# SimuRain_v1_0_UNO.net
KiCad netlist of a schematic drawn in EAGLE
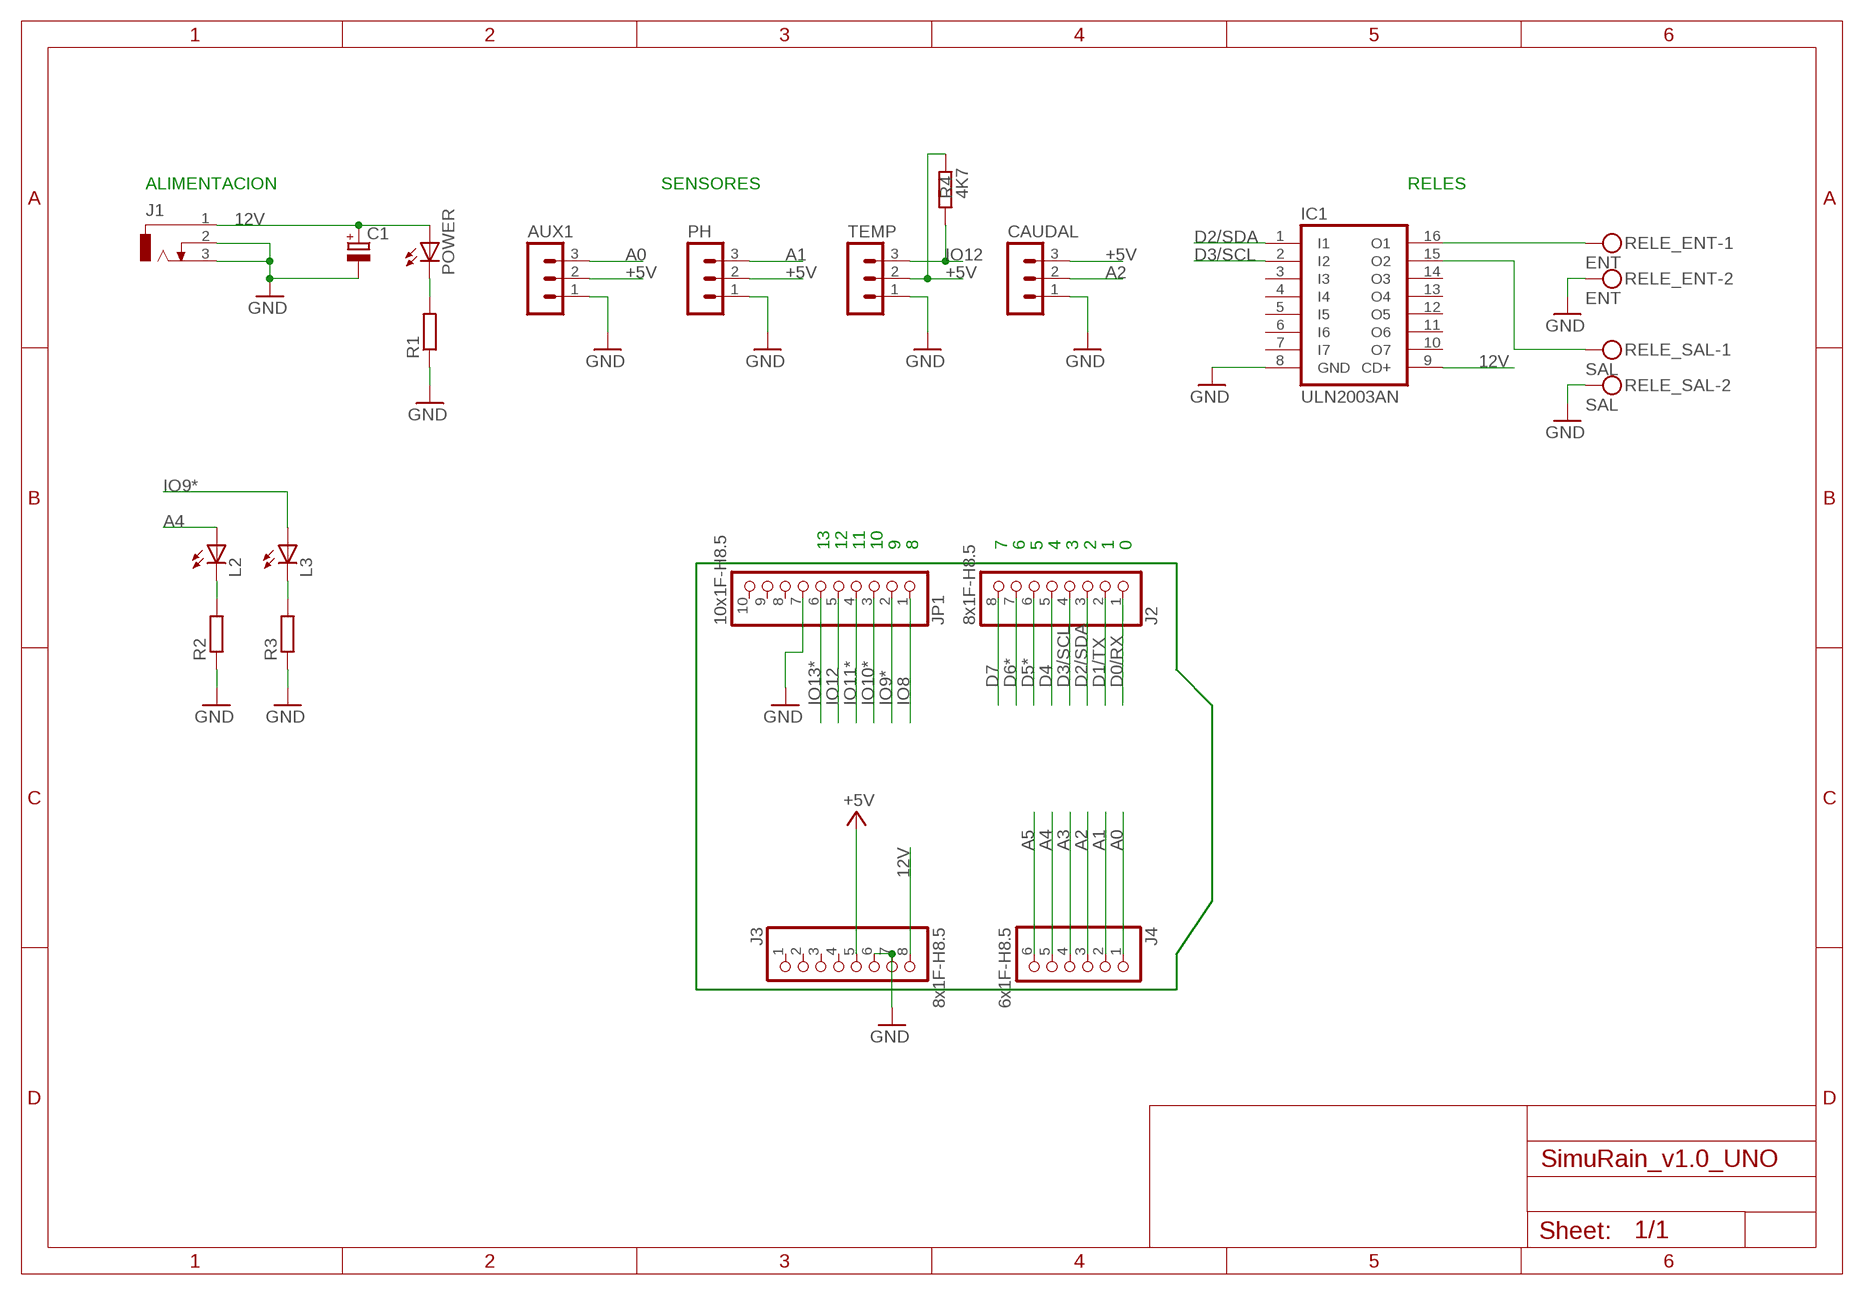
[diagram p0: schematic, sheet 1]

(export (version "E")
  (design (tool "Eeschema 10.0.6"))
  (components
    (comp (ref "AUX1")
      (value "MA03-1")
      (footprint "eagle-import:MA03-1")
      (libsource (lib "eagle-import") (part "MA03-1"))
    )
    (comp (ref "C1")
      (value "CPOL-EUE5-6")
      (footprint "eagle-import:E5-6")
      (libsource (lib "eagle-import") (part "CPOL-EUE5-6"))
    )
    (comp (ref "CAUDAL")
      (value "MA03-1")
      (footprint "eagle-import:MA03-1")
      (libsource (lib "eagle-import") (part "MA03-1"))
    )
    (comp (ref "IC1")
      (value "ULN2003AN")
      (footprint "eagle-import:DIL16")
      (libsource (lib "eagle-import") (part "ULN2003AN"))
    )
    (comp (ref "J1")
      (value "DCJ0303")
      (footprint "eagle-import:DCJ0303")
      (libsource (lib "eagle-import") (part "DCJ0303"))
    )
    (comp (ref "J2")
      (value "8x1F-H8.5")
      (footprint "eagle-import:1X08")
      (libsource (lib "eagle-import") (part "PINHD-1X8"))
    )
    (comp (ref "J3")
      (value "8x1F-H8.5")
      (footprint "eagle-import:1X08")
      (libsource (lib "eagle-import") (part "PINHD-1X8"))
    )
    (comp (ref "J4")
      (value "6x1F-H8.5")
      (footprint "eagle-import:1X06")
      (libsource (lib "eagle-import") (part "PINHD-1X6"))
    )
    (comp (ref "JP1")
      (value "10x1F-H8.5")
      (footprint "eagle-import:1X10")
      (libsource (lib "eagle-import") (part "PINHD-1X10"))
    )
    (comp (ref "L2")
      (value "LED5MM")
      (footprint "eagle-import:LED5MM")
      (libsource (lib "eagle-import") (part "LED5MM"))
    )
    (comp (ref "L3")
      (value "LED5MM")
      (footprint "eagle-import:LED5MM")
      (libsource (lib "eagle-import") (part "LED5MM"))
    )
    (comp (ref "PH")
      (value "MA03-1")
      (footprint "eagle-import:MA03-1")
      (libsource (lib "eagle-import") (part "MA03-1"))
    )
    (comp (ref "POWER")
      (value "LED5MM")
      (footprint "eagle-import:LED5MM")
      (libsource (lib "eagle-import") (part "LED5MM"))
    )
    (comp (ref "R1")
      (value "R-EU_0204/5")
      (footprint "eagle-import:0204_5")
      (libsource (lib "eagle-import") (part "R-EU_0204/5"))
    )
    (comp (ref "R2")
      (value "R-EU_0204/5")
      (footprint "eagle-import:0204_5")
      (libsource (lib "eagle-import") (part "R-EU_0204/5"))
    )
    (comp (ref "R3")
      (value "R-EU_0204/5")
      (footprint "eagle-import:0204_5")
      (libsource (lib "eagle-import") (part "R-EU_0204/5"))
    )
    (comp (ref "R4")
      (value "4K7")
      (footprint "eagle-import:0204_5")
      (libsource (lib "eagle-import") (part "R-EU_0204/5"))
    )
    (comp (ref "RELE_ENT")
      (value "ENT")
      (footprint "eagle-import:MKDSN1,5_2-5,08")
      (libsource (lib "eagle-import") (part "MKDSN1,5/2-5,08"))
    )
    (comp (ref "RELE_SAL")
      (value "SAL")
      (footprint "eagle-import:MKDSN1,5_2-5,08")
      (libsource (lib "eagle-import") (part "MKDSN1,5/2-5,08"))
    )
    (comp (ref "TEMP")
      (value "MA03-1")
      (footprint "eagle-import:MA03-1")
      (libsource (lib "eagle-import") (part "MA03-1"))
    )
  )
  (nets
    (net (code "1") (name "+5V") (class "Default")
      (node (ref "AUX1") (pin "2") (pinfunction "2_2") (pintype "passive"))
      (node (ref "CAUDAL") (pin "3") (pinfunction "3_3") (pintype "passive"))
      (node (ref "J3") (pin "5") (pinfunction "5_5") (pintype "passive"))
      (node (ref "PH") (pin "2") (pinfunction "2_2") (pintype "passive"))
      (node (ref "R4") (pin "2") (pinfunction "2_2") (pintype "passive"))
      (node (ref "TEMP") (pin "2") (pinfunction "2_2") (pintype "passive"))
    )
    (net (code "2") (name "/12V") (class "Default")
      (node (ref "C1") (pin "+") (pinfunction "+_+") (pintype "passive"))
      (node (ref "IC1") (pin "9") (pinfunction "CD+_9") (pintype "passive"))
      (node (ref "J1") (pin "1") (pinfunction "1_1") (pintype "passive"))
      (node (ref "J3") (pin "8") (pinfunction "8_8") (pintype "passive"))
      (node (ref "POWER") (pin "A") (pinfunction "A_A") (pintype "passive"))
    )
    (net (code "3") (name "/A0") (class "Default")
      (node (ref "AUX1") (pin "3") (pinfunction "3_3") (pintype "passive"))
      (node (ref "J4") (pin "1") (pinfunction "1_1") (pintype "passive"))
    )
    (net (code "4") (name "/A1") (class "Default")
      (node (ref "J4") (pin "2") (pinfunction "2_2") (pintype "passive"))
      (node (ref "PH") (pin "3") (pinfunction "3_3") (pintype "passive"))
    )
    (net (code "5") (name "/A2") (class "Default")
      (node (ref "CAUDAL") (pin "2") (pinfunction "2_2") (pintype "passive"))
      (node (ref "J4") (pin "3") (pinfunction "3_3") (pintype "passive"))
    )
    (net (code "6") (name "/A3") (class "Default")
      (node (ref "J4") (pin "4") (pinfunction "4_4") (pintype "passive"))
    )
    (net (code "7") (name "/A4") (class "Default")
      (node (ref "J4") (pin "5") (pinfunction "5_5") (pintype "passive"))
      (node (ref "L2") (pin "A") (pinfunction "A_A") (pintype "passive"))
    )
    (net (code "8") (name "/A5") (class "Default")
      (node (ref "J4") (pin "6") (pinfunction "6_6") (pintype "passive"))
    )
    (net (code "9") (name "/D0{slash}RX") (class "Default")
      (node (ref "J2") (pin "1") (pinfunction "1_1") (pintype "passive"))
    )
    (net (code "10") (name "/D1{slash}TX") (class "Default")
      (node (ref "J2") (pin "2") (pinfunction "2_2") (pintype "passive"))
    )
    (net (code "11") (name "/D2{slash}SDA") (class "Default")
      (node (ref "IC1") (pin "1") (pinfunction "I1_1") (pintype "input"))
      (node (ref "J2") (pin "3") (pinfunction "3_3") (pintype "passive"))
    )
    (net (code "12") (name "/D3{slash}SCL") (class "Default")
      (node (ref "IC1") (pin "2") (pinfunction "I2_2") (pintype "input"))
      (node (ref "J2") (pin "4") (pinfunction "4_4") (pintype "passive"))
    )
    (net (code "13") (name "/D4") (class "Default")
      (node (ref "J2") (pin "5") (pinfunction "5_5") (pintype "passive"))
    )
    (net (code "14") (name "/D5*") (class "Default")
      (node (ref "J2") (pin "6") (pinfunction "6_6") (pintype "passive"))
    )
    (net (code "15") (name "/D6*") (class "Default")
      (node (ref "J2") (pin "7") (pinfunction "7_7") (pintype "passive"))
    )
    (net (code "16") (name "/D7") (class "Default")
      (node (ref "J2") (pin "8") (pinfunction "8_8") (pintype "passive"))
    )
    (net (code "17") (name "/IO8") (class "Default")
      (node (ref "JP1") (pin "1") (pinfunction "1_1") (pintype "passive"))
    )
    (net (code "18") (name "/IO9*") (class "Default")
      (node (ref "JP1") (pin "2") (pinfunction "2_2") (pintype "passive"))
      (node (ref "L3") (pin "A") (pinfunction "A_A") (pintype "passive"))
    )
    (net (code "19") (name "/IO10*") (class "Default")
      (node (ref "JP1") (pin "3") (pinfunction "3_3") (pintype "passive"))
    )
    (net (code "20") (name "/IO11*") (class "Default")
      (node (ref "JP1") (pin "4") (pinfunction "4_4") (pintype "passive"))
    )
    (net (code "21") (name "/IO12") (class "Default")
      (node (ref "JP1") (pin "5") (pinfunction "5_5") (pintype "passive"))
      (node (ref "R4") (pin "1") (pinfunction "1_1") (pintype "passive"))
      (node (ref "TEMP") (pin "3") (pinfunction "3_3") (pintype "passive"))
    )
    (net (code "22") (name "/IO13*") (class "Default")
      (node (ref "JP1") (pin "6") (pinfunction "6_6") (pintype "passive"))
    )
    (net (code "23") (name "GND") (class "Default")
      (node (ref "AUX1") (pin "1") (pinfunction "1_1") (pintype "passive"))
      (node (ref "C1") (pin "-") (pinfunction "-_-") (pintype "passive"))
      (node (ref "CAUDAL") (pin "1") (pinfunction "1_1") (pintype "passive"))
      (node (ref "IC1") (pin "8") (pinfunction "GND_8") (pintype "power_in"))
      (node (ref "J1") (pin "2") (pinfunction "2_2") (pintype "passive"))
      (node (ref "J1") (pin "3") (pinfunction "3_3") (pintype "passive"))
      (node (ref "J3") (pin "6") (pinfunction "6_6") (pintype "passive"))
      (node (ref "J3") (pin "7") (pinfunction "7_7") (pintype "passive"))
      (node (ref "JP1") (pin "7") (pinfunction "7_7") (pintype "passive"))
      (node (ref "PH") (pin "1") (pinfunction "1_1") (pintype "passive"))
      (node (ref "R1") (pin "1") (pinfunction "1_1") (pintype "passive"))
      (node (ref "R2") (pin "1") (pinfunction "1_1") (pintype "passive"))
      (node (ref "R3") (pin "1") (pinfunction "1_1") (pintype "passive"))
      (node (ref "RELE_ENT") (pin "2") (pinfunction "KL_2") (pintype "passive"))
      (node (ref "RELE_SAL") (pin "2") (pinfunction "KL_2") (pintype "passive"))
      (node (ref "TEMP") (pin "1") (pinfunction "1_1") (pintype "passive"))
    )
    (net (code "24") (name "Net-(IC1-O1)") (class "Default")
      (node (ref "IC1") (pin "16") (pinfunction "O1_16") (pintype "open_collector"))
      (node (ref "RELE_ENT") (pin "1") (pinfunction "KL_1") (pintype "passive"))
    )
    (net (code "25") (name "Net-(IC1-O2)") (class "Default")
      (node (ref "IC1") (pin "15") (pinfunction "O2_15") (pintype "open_collector"))
      (node (ref "RELE_SAL") (pin "1") (pinfunction "KL_1") (pintype "passive"))
    )
    (net (code "26") (name "Net-(L2-C)") (class "Default")
      (node (ref "L2") (pin "K") (pinfunction "C_K") (pintype "passive"))
      (node (ref "R2") (pin "2") (pinfunction "2_2") (pintype "passive"))
    )
    (net (code "27") (name "Net-(L3-C)") (class "Default")
      (node (ref "L3") (pin "K") (pinfunction "C_K") (pintype "passive"))
      (node (ref "R3") (pin "2") (pinfunction "2_2") (pintype "passive"))
    )
    (net (code "28") (name "Net-(POWER-C)") (class "Default")
      (node (ref "POWER") (pin "K") (pinfunction "C_K") (pintype "passive"))
      (node (ref "R1") (pin "2") (pinfunction "2_2") (pintype "passive"))
    )
    (net (code "29") (name "unconnected-(IC1-I3-Pad3)") (class "Default")
      (node (ref "IC1") (pin "3") (pinfunction "I3_3") (pintype "input"))
    )
    (net (code "30") (name "unconnected-(IC1-I4-Pad4)") (class "Default")
      (node (ref "IC1") (pin "4") (pinfunction "I4_4") (pintype "input"))
    )
    (net (code "31") (name "unconnected-(IC1-I5-Pad5)") (class "Default")
      (node (ref "IC1") (pin "5") (pinfunction "I5_5") (pintype "input"))
    )
    (net (code "32") (name "unconnected-(IC1-I6-Pad6)") (class "Default")
      (node (ref "IC1") (pin "6") (pinfunction "I6_6") (pintype "input"))
    )
    (net (code "33") (name "unconnected-(IC1-I7-Pad7)") (class "Default")
      (node (ref "IC1") (pin "7") (pinfunction "I7_7") (pintype "input"))
    )
    (net (code "34") (name "unconnected-(IC1-O3-Pad14)") (class "Default")
      (node (ref "IC1") (pin "14") (pinfunction "O3_14") (pintype "open_collector"))
    )
    (net (code "35") (name "unconnected-(IC1-O4-Pad13)") (class "Default")
      (node (ref "IC1") (pin "13") (pinfunction "O4_13") (pintype "open_collector"))
    )
    (net (code "36") (name "unconnected-(IC1-O5-Pad12)") (class "Default")
      (node (ref "IC1") (pin "12") (pinfunction "O5_12") (pintype "open_collector"))
    )
    (net (code "37") (name "unconnected-(IC1-O6-Pad11)") (class "Default")
      (node (ref "IC1") (pin "11") (pinfunction "O6_11") (pintype "open_collector"))
    )
    (net (code "38") (name "unconnected-(IC1-O7-Pad10)") (class "Default")
      (node (ref "IC1") (pin "10") (pinfunction "O7_10") (pintype "open_collector"))
    )
    (net (code "39") (name "unconnected-(J3-Pad1)") (class "Default")
      (node (ref "J3") (pin "1") (pinfunction "1_1") (pintype "passive"))
    )
    (net (code "40") (name "unconnected-(J3-Pad2)") (class "Default")
      (node (ref "J3") (pin "2") (pinfunction "2_2") (pintype "passive"))
    )
    (net (code "41") (name "unconnected-(J3-Pad3)") (class "Default")
      (node (ref "J3") (pin "3") (pinfunction "3_3") (pintype "passive"))
    )
    (net (code "42") (name "unconnected-(J3-Pad4)") (class "Default")
      (node (ref "J3") (pin "4") (pinfunction "4_4") (pintype "passive"))
    )
    (net (code "43") (name "unconnected-(JP1-Pad8)") (class "Default")
      (node (ref "JP1") (pin "8") (pinfunction "8_8") (pintype "passive"))
    )
    (net (code "44") (name "unconnected-(JP1-Pad9)") (class "Default")
      (node (ref "JP1") (pin "9") (pinfunction "9_9") (pintype "passive"))
    )
    (net (code "45") (name "unconnected-(JP1-Pad10)") (class "Default")
      (node (ref "JP1") (pin "10") (pinfunction "10_10") (pintype "passive"))
    )
  )
)
